# Board_Schematic.net
KiCad netlist of a schematic drawn in Altium Designer
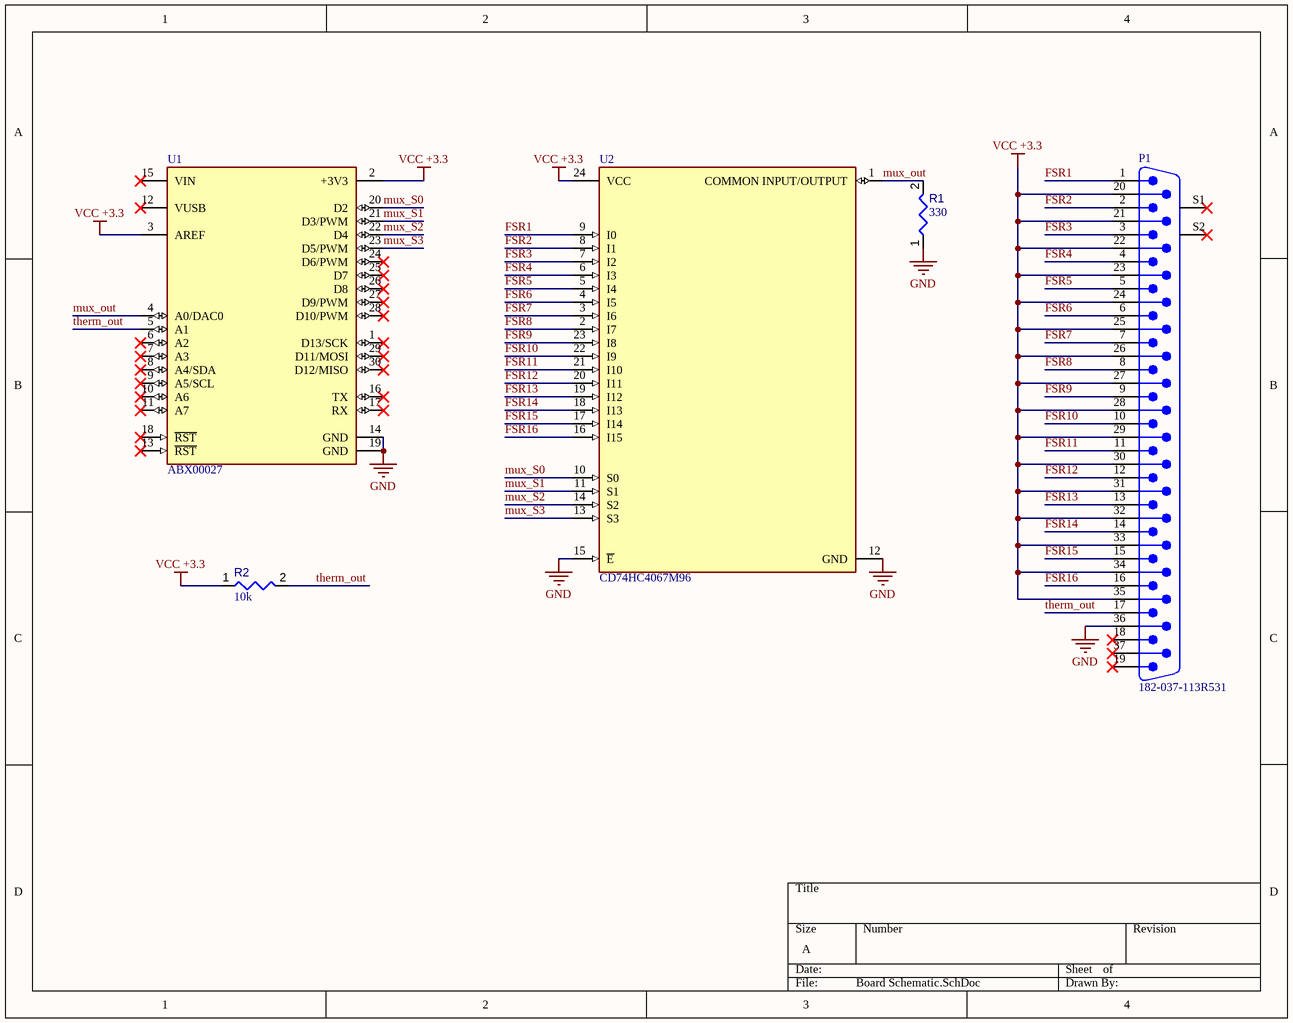
[diagram p0: Board Schematic.SchDoc]

(export (version "E")
  (design (tool "Eeschema 10.0.6"))
  (components
    (comp (ref "P1")
      (value "182-037-113R531")
      (footprint "NORCO-182-037-113R531_V")
      (description "Conn D-Subminiature M 37 POS 2.77mm Solder RA Thru-Hole 37 Terminal 1 Port")
      (libsource (lib ")") (part "NORCO-182-037-113R531"))
    )
    (comp (ref "R1")
      (value "330")
      (footprint "FP-ERJS08-MFG")
      (description "Res Thick Film 1206 330 Ohm 1% 0.25W ±100ppm/°C Molded SMD Punched Carrier T/R")
      (fields (field (name "TOLERANCE") "1%") (field (name "Comment") "ERJ-S08F3300V"))
      (libsource (lib ")") (part "RES-2"))
    )
    (comp (ref "R2")
      (value "10k")
      (footprint "RESC3216X60X45ML10T20")
      (description "250mW Thick Film Resistors 200V ±5% ±200ppm/℃ 10kΩ 1206 Chip Resistor - Surface Mount ROHS")
      (fields (field (name "TOLERANCE") "5%") (field (name "Comment") "CRCW120610K0JNEA"))
      (libsource (lib ")") (part "RES-2"))
    )
    (comp (ref "U1")
      (value "ABX00027")
      (footprint "FP-ABX00027-MFG")
      (description "SBC, Arduino Nano 33 IOT, SAMD21G18A, 32bit, 32KB RAM, 256KB Flash, 14 I/O pins")
      (libsource (lib ")") (part "83865d8401fbc65f0878695ee57b7b2"))
    )
    (comp (ref "U2")
      (value "CD74HC4067M96")
      (footprint "FP-DW0024A-IPC_C")
      (description "5V, 16:1 mux, single channel analog multiplexer, 24-SOIC, -55 to 125C")
      (libsource (lib ")") (part "0e3014a41e7f600214dac1b4fa06845"))
    )
  )
  (nets
    (net (code "1") (name "/FSR1") (class "Default")
      (node (ref "P1") (pin "1") (pinfunction "1_1") (pintype "passive"))
      (node (ref "U2") (pin "9") (pinfunction "I0_9") (pintype "input"))
    )
    (net (code "2") (name "/FSR2") (class "Default")
      (node (ref "P1") (pin "2") (pinfunction "2_2") (pintype "passive"))
      (node (ref "U2") (pin "8") (pinfunction "I1_8") (pintype "input"))
    )
    (net (code "3") (name "/FSR3") (class "Default")
      (node (ref "P1") (pin "3") (pinfunction "3_3") (pintype "passive"))
      (node (ref "U2") (pin "7") (pinfunction "I2_7") (pintype "input"))
    )
    (net (code "4") (name "/FSR4") (class "Default")
      (node (ref "P1") (pin "4") (pinfunction "4_4") (pintype "passive"))
      (node (ref "U2") (pin "6") (pinfunction "I3_6") (pintype "input"))
    )
    (net (code "5") (name "/FSR5") (class "Default")
      (node (ref "P1") (pin "5") (pinfunction "5_5") (pintype "passive"))
      (node (ref "U2") (pin "5") (pinfunction "I4_5") (pintype "input"))
    )
    (net (code "6") (name "/FSR6") (class "Default")
      (node (ref "P1") (pin "6") (pinfunction "6_6") (pintype "passive"))
      (node (ref "U2") (pin "4") (pinfunction "I5_4") (pintype "input"))
    )
    (net (code "7") (name "/FSR7") (class "Default")
      (node (ref "P1") (pin "7") (pinfunction "7_7") (pintype "passive"))
      (node (ref "U2") (pin "3") (pinfunction "I6_3") (pintype "input"))
    )
    (net (code "8") (name "/FSR8") (class "Default")
      (node (ref "P1") (pin "8") (pinfunction "8_8") (pintype "passive"))
      (node (ref "U2") (pin "2") (pinfunction "I7_2") (pintype "input"))
    )
    (net (code "9") (name "/FSR9") (class "Default")
      (node (ref "P1") (pin "9") (pinfunction "9_9") (pintype "passive"))
      (node (ref "U2") (pin "23") (pinfunction "I8_23") (pintype "input"))
    )
    (net (code "10") (name "/FSR10") (class "Default")
      (node (ref "P1") (pin "10") (pinfunction "10_10") (pintype "passive"))
      (node (ref "U2") (pin "22") (pinfunction "I9_22") (pintype "input"))
    )
    (net (code "11") (name "/FSR11") (class "Default")
      (node (ref "P1") (pin "11") (pinfunction "11_11") (pintype "passive"))
      (node (ref "U2") (pin "21") (pinfunction "I10_21") (pintype "input"))
    )
    (net (code "12") (name "/FSR12") (class "Default")
      (node (ref "P1") (pin "12") (pinfunction "12_12") (pintype "passive"))
      (node (ref "U2") (pin "20") (pinfunction "I11_20") (pintype "input"))
    )
    (net (code "13") (name "/FSR13") (class "Default")
      (node (ref "P1") (pin "13") (pinfunction "13_13") (pintype "passive"))
      (node (ref "U2") (pin "19") (pinfunction "I12_19") (pintype "input"))
    )
    (net (code "14") (name "/FSR14") (class "Default")
      (node (ref "P1") (pin "14") (pinfunction "14_14") (pintype "passive"))
      (node (ref "U2") (pin "18") (pinfunction "I13_18") (pintype "input"))
    )
    (net (code "15") (name "/FSR15") (class "Default")
      (node (ref "P1") (pin "15") (pinfunction "15_15") (pintype "passive"))
      (node (ref "U2") (pin "17") (pinfunction "I14_17") (pintype "input"))
    )
    (net (code "16") (name "/FSR16") (class "Default")
      (node (ref "P1") (pin "16") (pinfunction "16_16") (pintype "passive"))
      (node (ref "U2") (pin "16") (pinfunction "I15_16") (pintype "input"))
    )
    (net (code "17") (name "/mux_S0") (class "Default")
      (node (ref "U1") (pin "20") (pinfunction "D2_20") (pintype "bidirectional"))
      (node (ref "U2") (pin "10") (pinfunction "S0_10") (pintype "input"))
    )
    (net (code "18") (name "/mux_S1") (class "Default")
      (node (ref "U1") (pin "21") (pinfunction "D3/PWM_21") (pintype "bidirectional"))
      (node (ref "U2") (pin "11") (pinfunction "S1_11") (pintype "input"))
    )
    (net (code "19") (name "/mux_S2") (class "Default")
      (node (ref "U1") (pin "22") (pinfunction "D4_22") (pintype "bidirectional"))
      (node (ref "U2") (pin "14") (pinfunction "S2_14") (pintype "input"))
    )
    (net (code "20") (name "/mux_S3") (class "Default")
      (node (ref "U1") (pin "23") (pinfunction "D5/PWM_23") (pintype "bidirectional"))
      (node (ref "U2") (pin "13") (pinfunction "S3_13") (pintype "input"))
    )
    (net (code "21") (name "/mux_out") (class "Default")
      (node (ref "R1") (pin "2") (pinfunction "2_2") (pintype "passive"))
      (node (ref "U1") (pin "4") (pinfunction "A0/DAC0_4") (pintype "bidirectional"))
      (node (ref "U2") (pin "1") (pinfunction "COMMON_INPUT/OUTPUT_1") (pintype "bidirectional"))
    )
    (net (code "22") (name "/therm_out") (class "Default")
      (node (ref "P1") (pin "17") (pinfunction "17_17") (pintype "passive"))
      (node (ref "R2") (pin "2") (pinfunction "2_2") (pintype "passive"))
      (node (ref "U1") (pin "5") (pinfunction "A1_5") (pintype "bidirectional"))
    )
    (net (code "23") (name "GND") (class "Default")
      (node (ref "P1") (pin "36") (pinfunction "36_36") (pintype "passive"))
      (node (ref "R1") (pin "1") (pinfunction "1_1") (pintype "passive"))
      (node (ref "U1") (pin "14") (pinfunction "GND_14") (pintype "power_in"))
      (node (ref "U1") (pin "19") (pinfunction "GND_19") (pintype "power_in"))
      (node (ref "U2") (pin "12") (pinfunction "GND_12") (pintype "power_in"))
      (node (ref "U2") (pin "15") (pinfunction "~{E}_15") (pintype "input"))
    )
    (net (code "24") (name "VCC +3.3") (class "Default")
      (node (ref "P1") (pin "20") (pinfunction "20_20") (pintype "passive"))
      (node (ref "P1") (pin "21") (pinfunction "21_21") (pintype "passive"))
      (node (ref "P1") (pin "22") (pinfunction "22_22") (pintype "passive"))
      (node (ref "P1") (pin "23") (pinfunction "23_23") (pintype "passive"))
      (node (ref "P1") (pin "24") (pinfunction "24_24") (pintype "passive"))
      (node (ref "P1") (pin "25") (pinfunction "25_25") (pintype "passive"))
      (node (ref "P1") (pin "26") (pinfunction "26_26") (pintype "passive"))
      (node (ref "P1") (pin "27") (pinfunction "27_27") (pintype "passive"))
      (node (ref "P1") (pin "28") (pinfunction "28_28") (pintype "passive"))
      (node (ref "P1") (pin "29") (pinfunction "29_29") (pintype "passive"))
      (node (ref "P1") (pin "30") (pinfunction "30_30") (pintype "passive"))
      (node (ref "P1") (pin "31") (pinfunction "31_31") (pintype "passive"))
      (node (ref "P1") (pin "32") (pinfunction "32_32") (pintype "passive"))
      (node (ref "P1") (pin "33") (pinfunction "33_33") (pintype "passive"))
      (node (ref "P1") (pin "34") (pinfunction "34_34") (pintype "passive"))
      (node (ref "P1") (pin "35") (pinfunction "35_35") (pintype "passive"))
      (node (ref "R2") (pin "1") (pinfunction "1_1") (pintype "passive"))
      (node (ref "U1") (pin "2") (pinfunction "+3V3_2") (pintype "power_in"))
      (node (ref "U1") (pin "3") (pinfunction "AREF_3") (pintype "passive"))
      (node (ref "U2") (pin "24") (pinfunction "VCC_24") (pintype "power_in"))
    )
    (net (code "25") (name "unconnected-(P1-Pad18)") (class "Default")
      (node (ref "P1") (pin "18") (pinfunction "18_18") (pintype "passive+no_connect"))
    )
    (net (code "26") (name "unconnected-(P1-Pad19)") (class "Default")
      (node (ref "P1") (pin "19") (pinfunction "19_19") (pintype "passive+no_connect"))
    )
    (net (code "27") (name "unconnected-(P1-Pad37)") (class "Default")
      (node (ref "P1") (pin "37") (pinfunction "37_37") (pintype "passive+no_connect"))
    )
    (net (code "28") (name "unconnected-(P1-PadS1)") (class "Default")
      (node (ref "P1") (pin "S1") (pinfunction "S1_S1") (pintype "passive+no_connect"))
    )
    (net (code "29") (name "unconnected-(P1-PadS2)") (class "Default")
      (node (ref "P1") (pin "S2") (pinfunction "S2_S2") (pintype "passive+no_connect"))
    )
    (net (code "30") (name "unconnected-(U1-A2-Pad6)") (class "Default")
      (node (ref "U1") (pin "6") (pinfunction "A2_6") (pintype "bidirectional+no_connect"))
    )
    (net (code "31") (name "unconnected-(U1-A3-Pad7)") (class "Default")
      (node (ref "U1") (pin "7") (pinfunction "A3_7") (pintype "bidirectional+no_connect"))
    )
    (net (code "32") (name "unconnected-(U1-A4{slash}SDA-Pad8)") (class "Default")
      (node (ref "U1") (pin "8") (pinfunction "A4/SDA_8") (pintype "bidirectional+no_connect"))
    )
    (net (code "33") (name "unconnected-(U1-A5{slash}SCL-Pad9)") (class "Default")
      (node (ref "U1") (pin "9") (pinfunction "A5/SCL_9") (pintype "bidirectional+no_connect"))
    )
    (net (code "34") (name "unconnected-(U1-A6-Pad10)") (class "Default")
      (node (ref "U1") (pin "10") (pinfunction "A6_10") (pintype "bidirectional+no_connect"))
    )
    (net (code "35") (name "unconnected-(U1-A7-Pad11)") (class "Default")
      (node (ref "U1") (pin "11") (pinfunction "A7_11") (pintype "bidirectional+no_connect"))
    )
    (net (code "36") (name "unconnected-(U1-D6{slash}PWM-Pad24)") (class "Default")
      (node (ref "U1") (pin "24") (pinfunction "D6/PWM_24") (pintype "bidirectional+no_connect"))
    )
    (net (code "37") (name "unconnected-(U1-D7-Pad25)") (class "Default")
      (node (ref "U1") (pin "25") (pinfunction "D7_25") (pintype "bidirectional+no_connect"))
    )
    (net (code "38") (name "unconnected-(U1-D8-Pad26)") (class "Default")
      (node (ref "U1") (pin "26") (pinfunction "D8_26") (pintype "bidirectional+no_connect"))
    )
    (net (code "39") (name "unconnected-(U1-D9{slash}PWM-Pad27)") (class "Default")
      (node (ref "U1") (pin "27") (pinfunction "D9/PWM_27") (pintype "bidirectional+no_connect"))
    )
    (net (code "40") (name "unconnected-(U1-D10{slash}PWM-Pad28)") (class "Default")
      (node (ref "U1") (pin "28") (pinfunction "D10/PWM_28") (pintype "bidirectional+no_connect"))
    )
    (net (code "41") (name "unconnected-(U1-D11{slash}MOSI-Pad29)") (class "Default")
      (node (ref "U1") (pin "29") (pinfunction "D11/MOSI_29") (pintype "bidirectional+no_connect"))
    )
    (net (code "42") (name "unconnected-(U1-D12{slash}MISO-Pad30)") (class "Default")
      (node (ref "U1") (pin "30") (pinfunction "D12/MISO_30") (pintype "bidirectional+no_connect"))
    )
    (net (code "43") (name "unconnected-(U1-D13{slash}SCK-Pad1)") (class "Default")
      (node (ref "U1") (pin "1") (pinfunction "D13/SCK_1") (pintype "bidirectional+no_connect"))
    )
    (net (code "44") (name "unconnected-(U1-RX-Pad17)") (class "Default")
      (node (ref "U1") (pin "17") (pinfunction "RX_17") (pintype "bidirectional+no_connect"))
    )
    (net (code "45") (name "unconnected-(U1-TX-Pad16)") (class "Default")
      (node (ref "U1") (pin "16") (pinfunction "TX_16") (pintype "bidirectional+no_connect"))
    )
    (net (code "46") (name "unconnected-(U1-VIN-Pad15)") (class "Default")
      (node (ref "U1") (pin "15") (pinfunction "VIN_15") (pintype "power_in+no_connect"))
    )
    (net (code "47") (name "unconnected-(U1-VUSB-Pad12)") (class "Default")
      (node (ref "U1") (pin "12") (pinfunction "VUSB_12") (pintype "power_in+no_connect"))
    )
    (net (code "48") (name "unconnected-(U1-~{RST}-Pad13)") (class "Default")
      (node (ref "U1") (pin "13") (pinfunction "~{RST}_13") (pintype "input+no_connect"))
    )
    (net (code "49") (name "unconnected-(U1-~{RST}-Pad18)") (class "Default")
      (node (ref "U1") (pin "18") (pinfunction "~{RST}_18") (pintype "input+no_connect"))
    )
  )
)
